# Sheet1.net
KiCad netlist of a schematic drawn in Altium Designer
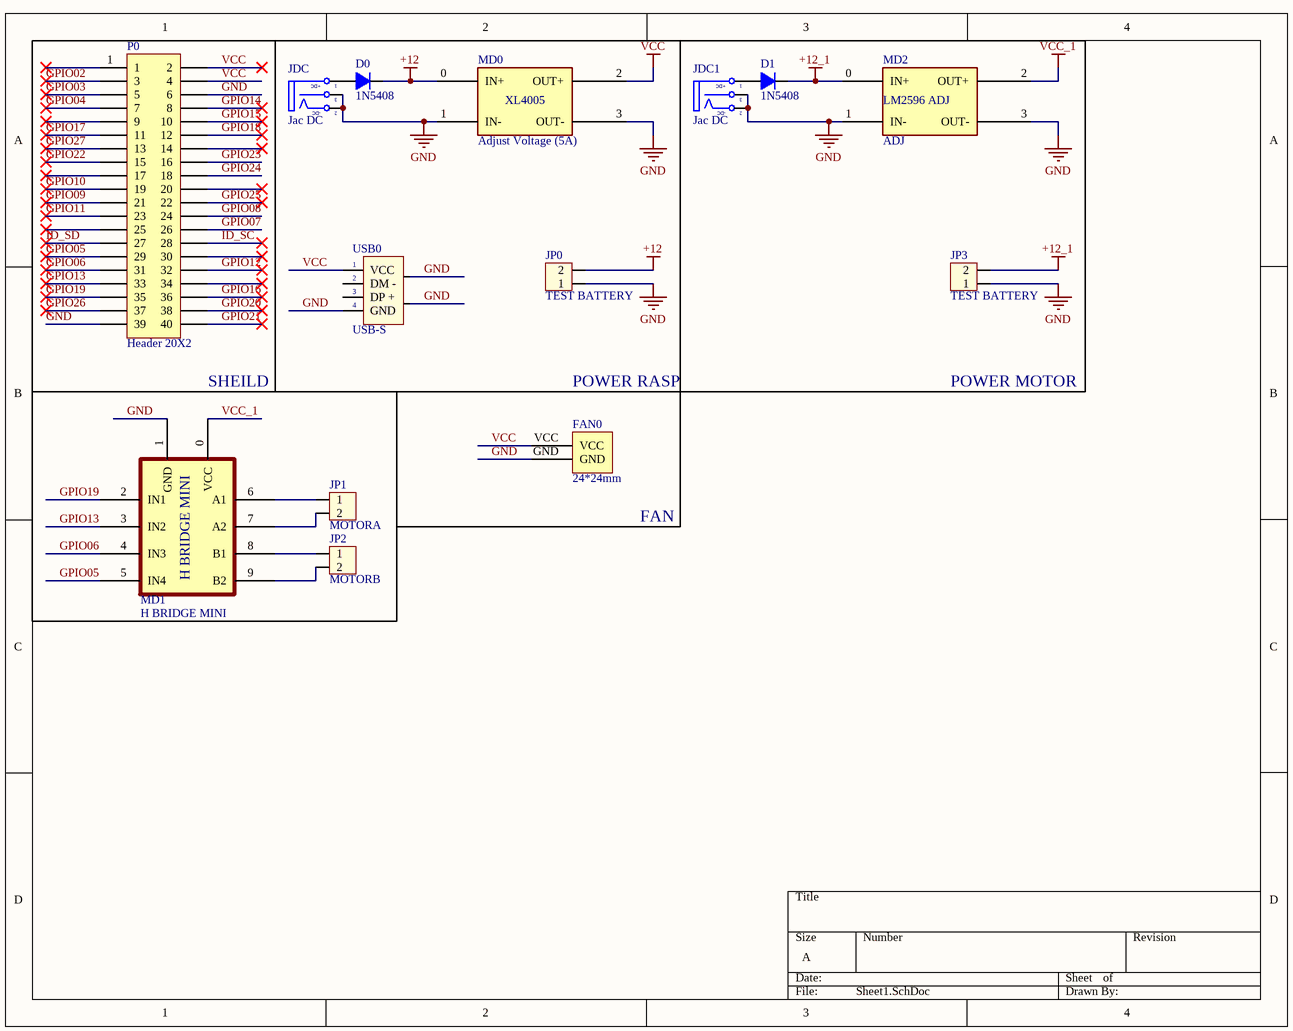
[diagram p0: Sheet1.SchDoc]

(export (version "E")
  (design (tool "Eeschema 10.0.6"))
  (components
    (comp (ref "D0")
      (value "1N5408")
      (footprint "D5A")
      (description "Diode 5A")
      (libsource (lib "syhaunguyen") (part "D5A"))
    )
    (comp (ref "D1")
      (value "1N5408")
      (footprint "D5A")
      (description "Diode 5A")
      (libsource (lib "syhaunguyen") (part "D5A"))
    )
    (comp (ref "FAN0") (value "24*24mm") (footprint "FAN DC") (libsource (lib "Mylib") (part "FAN 24*24mm")))
    (comp (ref "JDC")
      (value "Jac DC")
      (footprint "DC-IN")
      (description "Jac DC input")
      (libsource (lib "syhaunguyen") (part "DCIN"))
    )
    (comp (ref "JDC1")
      (value "Jac DC")
      (footprint "DC-IN")
      (description "Jac DC input")
      (libsource (lib "syhaunguyen") (part "DCIN"))
    )
    (comp (ref "JP0")
      (value "TEST BATTERY")
      (footprint "CON2")
      (description "Connector 2")
      (libsource (lib "syhaunguyen") (part "Con2"))
    )
    (comp (ref "JP1")
      (value "MOTORA")
      (footprint "CON2")
      (description "Connector 2")
      (libsource (lib "") (part "Con2_1"))
    )
    (comp (ref "JP2")
      (value "MOTORB")
      (footprint "CON2")
      (description "Connector 2")
      (libsource (lib "") (part "Con2_1"))
    )
    (comp (ref "JP3")
      (value "TEST BATTERY")
      (footprint "CON2")
      (description "Connector 2")
      (libsource (lib "syhaunguyen") (part "Con2"))
    )
    (comp (ref "MD0")
      (value "Adjust Voltage (5A)")
      (footprint "XL4005")
      (libsource (lib "Mylib") (part "XL4005"))
    )
    (comp (ref "MD1")
      (value "H BRIDGE MINI")
      (footprint "H BRIDGE MINI")
      (description "MX1508")
      (libsource (lib "Mylib") (part "H BRIDGE MINI"))
    )
    (comp (ref "MD2")
      (value "ADJ")
      (footprint "LM2596-ADJ")
      (description "Manage voltage")
      (libsource (lib "Mylib") (part "LM2596"))
    )
    (comp (ref "P0")
      (value "Header 20X2")
      (footprint "HDR2X20")
      (description "Header, 20-Pin, Dual row")
      (fields (field (name "PUBLISHER") "Altium Limited"))
      (libsource (lib "Miscellaneous Connectors") (part "Header 20X2"))
    )
    (comp (ref "USB0")
      (value "USB-S")
      (footprint "USB-A")
      (description "USB connector")
      (libsource (lib "syhaunguyen") (part "USB_S"))
    )
  )
  (nets
    (net (code "1") (name "+12") (class "Default")
      (node (ref "D0") (pin "2") (pinfunction "K_2") (pintype "passive"))
      (node (ref "JP0") (pin "2") (pinfunction "2_2") (pintype "passive"))
      (node (ref "MD0") (pin "0") (pinfunction "IN+_0") (pintype "power_in"))
    )
    (net (code "2") (name "+12_1") (class "Default")
      (node (ref "D1") (pin "2") (pinfunction "K_2") (pintype "passive"))
      (node (ref "JP3") (pin "2") (pinfunction "2_2") (pintype "passive"))
      (node (ref "MD2") (pin "0") (pinfunction "IN+_0") (pintype "power_in"))
    )
    (net (code "3") (name "/GPIO02") (class "Default")
      (node (ref "P0") (pin "3") (pinfunction "3_3") (pintype "passive+no_connect"))
    )
    (net (code "4") (name "/GPIO03") (class "Default")
      (node (ref "P0") (pin "5") (pinfunction "5_5") (pintype "passive+no_connect"))
    )
    (net (code "5") (name "/GPIO04") (class "Default")
      (node (ref "P0") (pin "7") (pinfunction "7_7") (pintype "passive+no_connect"))
    )
    (net (code "6") (name "/GPIO05") (class "Default")
      (node (ref "MD1") (pin "5") (pinfunction "IN4_5") (pintype "passive"))
      (node (ref "P0") (pin "29") (pinfunction "29_29") (pintype "passive"))
    )
    (net (code "7") (name "/GPIO06") (class "Default")
      (node (ref "MD1") (pin "4") (pinfunction "IN3_4") (pintype "passive"))
      (node (ref "P0") (pin "31") (pinfunction "31_31") (pintype "passive"))
    )
    (net (code "8") (name "/GPIO07") (class "Default")
      (node (ref "P0") (pin "26") (pinfunction "26_26") (pintype "passive"))
    )
    (net (code "9") (name "/GPIO08") (class "Default")
      (node (ref "P0") (pin "24") (pinfunction "24_24") (pintype "passive"))
    )
    (net (code "10") (name "/GPIO09") (class "Default")
      (node (ref "P0") (pin "21") (pinfunction "21_21") (pintype "passive+no_connect"))
    )
    (net (code "11") (name "/GPIO10") (class "Default")
      (node (ref "P0") (pin "19") (pinfunction "19_19") (pintype "passive+no_connect"))
    )
    (net (code "12") (name "/GPIO11") (class "Default")
      (node (ref "P0") (pin "23") (pinfunction "23_23") (pintype "passive+no_connect"))
    )
    (net (code "13") (name "/GPIO12") (class "Default")
      (node (ref "P0") (pin "32") (pinfunction "32_32") (pintype "passive+no_connect"))
    )
    (net (code "14") (name "/GPIO13") (class "Default")
      (node (ref "MD1") (pin "3") (pinfunction "IN2_3") (pintype "passive"))
      (node (ref "P0") (pin "33") (pinfunction "33_33") (pintype "passive"))
    )
    (net (code "15") (name "/GPIO14") (class "Default")
      (node (ref "P0") (pin "8") (pinfunction "8_8") (pintype "passive+no_connect"))
    )
    (net (code "16") (name "/GPIO15") (class "Default")
      (node (ref "P0") (pin "10") (pinfunction "10_10") (pintype "passive+no_connect"))
    )
    (net (code "17") (name "/GPIO16") (class "Default")
      (node (ref "P0") (pin "36") (pinfunction "36_36") (pintype "passive+no_connect"))
    )
    (net (code "18") (name "/GPIO17") (class "Default")
      (node (ref "P0") (pin "11") (pinfunction "11_11") (pintype "passive+no_connect"))
    )
    (net (code "19") (name "/GPIO18") (class "Default")
      (node (ref "P0") (pin "12") (pinfunction "12_12") (pintype "passive+no_connect"))
    )
    (net (code "20") (name "/GPIO19") (class "Default")
      (node (ref "MD1") (pin "2") (pinfunction "IN1_2") (pintype "passive"))
      (node (ref "P0") (pin "35") (pinfunction "35_35") (pintype "passive"))
    )
    (net (code "21") (name "/GPIO20") (class "Default")
      (node (ref "P0") (pin "38") (pinfunction "38_38") (pintype "passive+no_connect"))
    )
    (net (code "22") (name "/GPIO21") (class "Default")
      (node (ref "P0") (pin "40") (pinfunction "40_40") (pintype "passive+no_connect"))
    )
    (net (code "23") (name "/GPIO22") (class "Default")
      (node (ref "P0") (pin "15") (pinfunction "15_15") (pintype "passive+no_connect"))
    )
    (net (code "24") (name "/GPIO23") (class "Default")
      (node (ref "P0") (pin "16") (pinfunction "16_16") (pintype "passive"))
    )
    (net (code "25") (name "/GPIO24") (class "Default")
      (node (ref "P0") (pin "18") (pinfunction "18_18") (pintype "passive"))
    )
    (net (code "26") (name "/GPIO25") (class "Default")
      (node (ref "P0") (pin "22") (pinfunction "22_22") (pintype "passive+no_connect"))
    )
    (net (code "27") (name "/GPIO26") (class "Default")
      (node (ref "P0") (pin "37") (pinfunction "37_37") (pintype "passive+no_connect"))
    )
    (net (code "28") (name "/GPIO27") (class "Default")
      (node (ref "P0") (pin "13") (pinfunction "13_13") (pintype "passive+no_connect"))
    )
    (net (code "29") (name "/ID_SC") (class "Default")
      (node (ref "P0") (pin "28") (pinfunction "28_28") (pintype "passive+no_connect"))
    )
    (net (code "30") (name "/ID_SD") (class "Default")
      (node (ref "P0") (pin "27") (pinfunction "27_27") (pintype "passive+no_connect"))
    )
    (net (code "31") (name "GND") (class "Default")
      (node (ref "FAN0") (pin "GND") (pinfunction "GND_GND") (pintype "passive"))
      (node (ref "JDC") (pin "2") (pinfunction "TN_2") (pintype "passive"))
      (node (ref "JDC") (pin "3") (pinfunction "S_3") (pintype "power_in"))
      (node (ref "JDC1") (pin "2") (pinfunction "TN_2") (pintype "passive"))
      (node (ref "JDC1") (pin "3") (pinfunction "S_3") (pintype "power_in"))
      (node (ref "JP0") (pin "1") (pinfunction "1_1") (pintype "passive"))
      (node (ref "JP3") (pin "1") (pinfunction "1_1") (pintype "passive"))
      (node (ref "MD0") (pin "1") (pinfunction "IN-_1") (pintype "power_in"))
      (node (ref "MD0") (pin "3") (pinfunction "OUT-_3") (pintype "power_in"))
      (node (ref "MD1") (pin "1") (pinfunction "GND_1") (pintype "passive"))
      (node (ref "MD2") (pin "1") (pinfunction "IN-_1") (pintype "power_in"))
      (node (ref "MD2") (pin "3") (pinfunction "OUT-_3") (pintype "power_in"))
      (node (ref "P0") (pin "39") (pinfunction "39_39") (pintype "passive"))
      (node (ref "P0") (pin "6") (pinfunction "6_6") (pintype "passive"))
      (node (ref "USB0") (pin "4") (pinfunction "GND_4") (pintype "passive"))
      (node (ref "USB0") (pin "5") (pinfunction "5_5") (pintype "passive"))
      (node (ref "USB0") (pin "6") (pinfunction "6_6") (pintype "passive"))
    )
    (net (code "32") (name "Net-(D0-A)") (class "Default")
      (node (ref "D0") (pin "1") (pinfunction "A_1") (pintype "passive"))
      (node (ref "JDC") (pin "1") (pinfunction "T_1") (pintype "passive"))
    )
    (net (code "33") (name "Net-(D1-A)") (class "Default")
      (node (ref "D1") (pin "1") (pinfunction "A_1") (pintype "passive"))
      (node (ref "JDC1") (pin "1") (pinfunction "T_1") (pintype "passive"))
    )
    (net (code "34") (name "Net-(MD1-A1)") (class "Default")
      (node (ref "JP1") (pin "1") (pinfunction "1_1") (pintype "passive"))
      (node (ref "MD1") (pin "6") (pinfunction "A1_6") (pintype "passive"))
    )
    (net (code "35") (name "Net-(MD1-A2)") (class "Default")
      (node (ref "JP1") (pin "2") (pinfunction "2_2") (pintype "passive"))
      (node (ref "MD1") (pin "7") (pinfunction "A2_7") (pintype "passive"))
    )
    (net (code "36") (name "Net-(MD1-B1)") (class "Default")
      (node (ref "JP2") (pin "1") (pinfunction "1_1") (pintype "passive"))
      (node (ref "MD1") (pin "8") (pinfunction "B1_8") (pintype "passive"))
    )
    (net (code "37") (name "Net-(MD1-B2)") (class "Default")
      (node (ref "JP2") (pin "2") (pinfunction "2_2") (pintype "passive"))
      (node (ref "MD1") (pin "9") (pinfunction "B2_9") (pintype "passive"))
    )
    (net (code "38") (name "VCC") (class "Default")
      (node (ref "FAN0") (pin "VCC") (pinfunction "VCC_VCC") (pintype "passive"))
      (node (ref "MD0") (pin "2") (pinfunction "OUT+_2") (pintype "power_in"))
      (node (ref "P0") (pin "2") (pinfunction "2_2") (pintype "passive"))
      (node (ref "P0") (pin "4") (pinfunction "4_4") (pintype "passive"))
      (node (ref "USB0") (pin "1") (pinfunction "VCC_1") (pintype "passive"))
    )
    (net (code "39") (name "VCC_1") (class "Default")
      (node (ref "MD1") (pin "0") (pinfunction "VCC_0") (pintype "passive"))
      (node (ref "MD2") (pin "2") (pinfunction "OUT+_2") (pintype "power_in"))
    )
    (net (code "40") (name "unconnected-(P0-Pad1)") (class "Default")
      (node (ref "P0") (pin "1") (pinfunction "1_1") (pintype "passive+no_connect"))
    )
    (net (code "41") (name "unconnected-(P0-Pad9)") (class "Default")
      (node (ref "P0") (pin "9") (pinfunction "9_9") (pintype "passive+no_connect"))
    )
    (net (code "42") (name "unconnected-(P0-Pad14)") (class "Default")
      (node (ref "P0") (pin "14") (pinfunction "14_14") (pintype "passive+no_connect"))
    )
    (net (code "43") (name "unconnected-(P0-Pad17)") (class "Default")
      (node (ref "P0") (pin "17") (pinfunction "17_17") (pintype "passive+no_connect"))
    )
    (net (code "44") (name "unconnected-(P0-Pad20)") (class "Default")
      (node (ref "P0") (pin "20") (pinfunction "20_20") (pintype "passive+no_connect"))
    )
    (net (code "45") (name "unconnected-(P0-Pad25)") (class "Default")
      (node (ref "P0") (pin "25") (pinfunction "25_25") (pintype "passive+no_connect"))
    )
    (net (code "46") (name "unconnected-(P0-Pad30)") (class "Default")
      (node (ref "P0") (pin "30") (pinfunction "30_30") (pintype "passive+no_connect"))
    )
    (net (code "47") (name "unconnected-(P0-Pad34)") (class "Default")
      (node (ref "P0") (pin "34") (pinfunction "34_34") (pintype "passive+no_connect"))
    )
    (net (code "48") (name "unconnected-(USB0-DM_--Pad2)") (class "Default")
      (node (ref "USB0") (pin "2") (pinfunction "DM_-_2") (pintype "passive"))
    )
    (net (code "49") (name "unconnected-(USB0-DP_+-Pad3)") (class "Default")
      (node (ref "USB0") (pin "3") (pinfunction "DP_+_3") (pintype "passive"))
    )
  )
)
